# SCH_Breakout_Boards_2023-05-21.net
KiCad netlist of a schematic drawn in EasyEDA
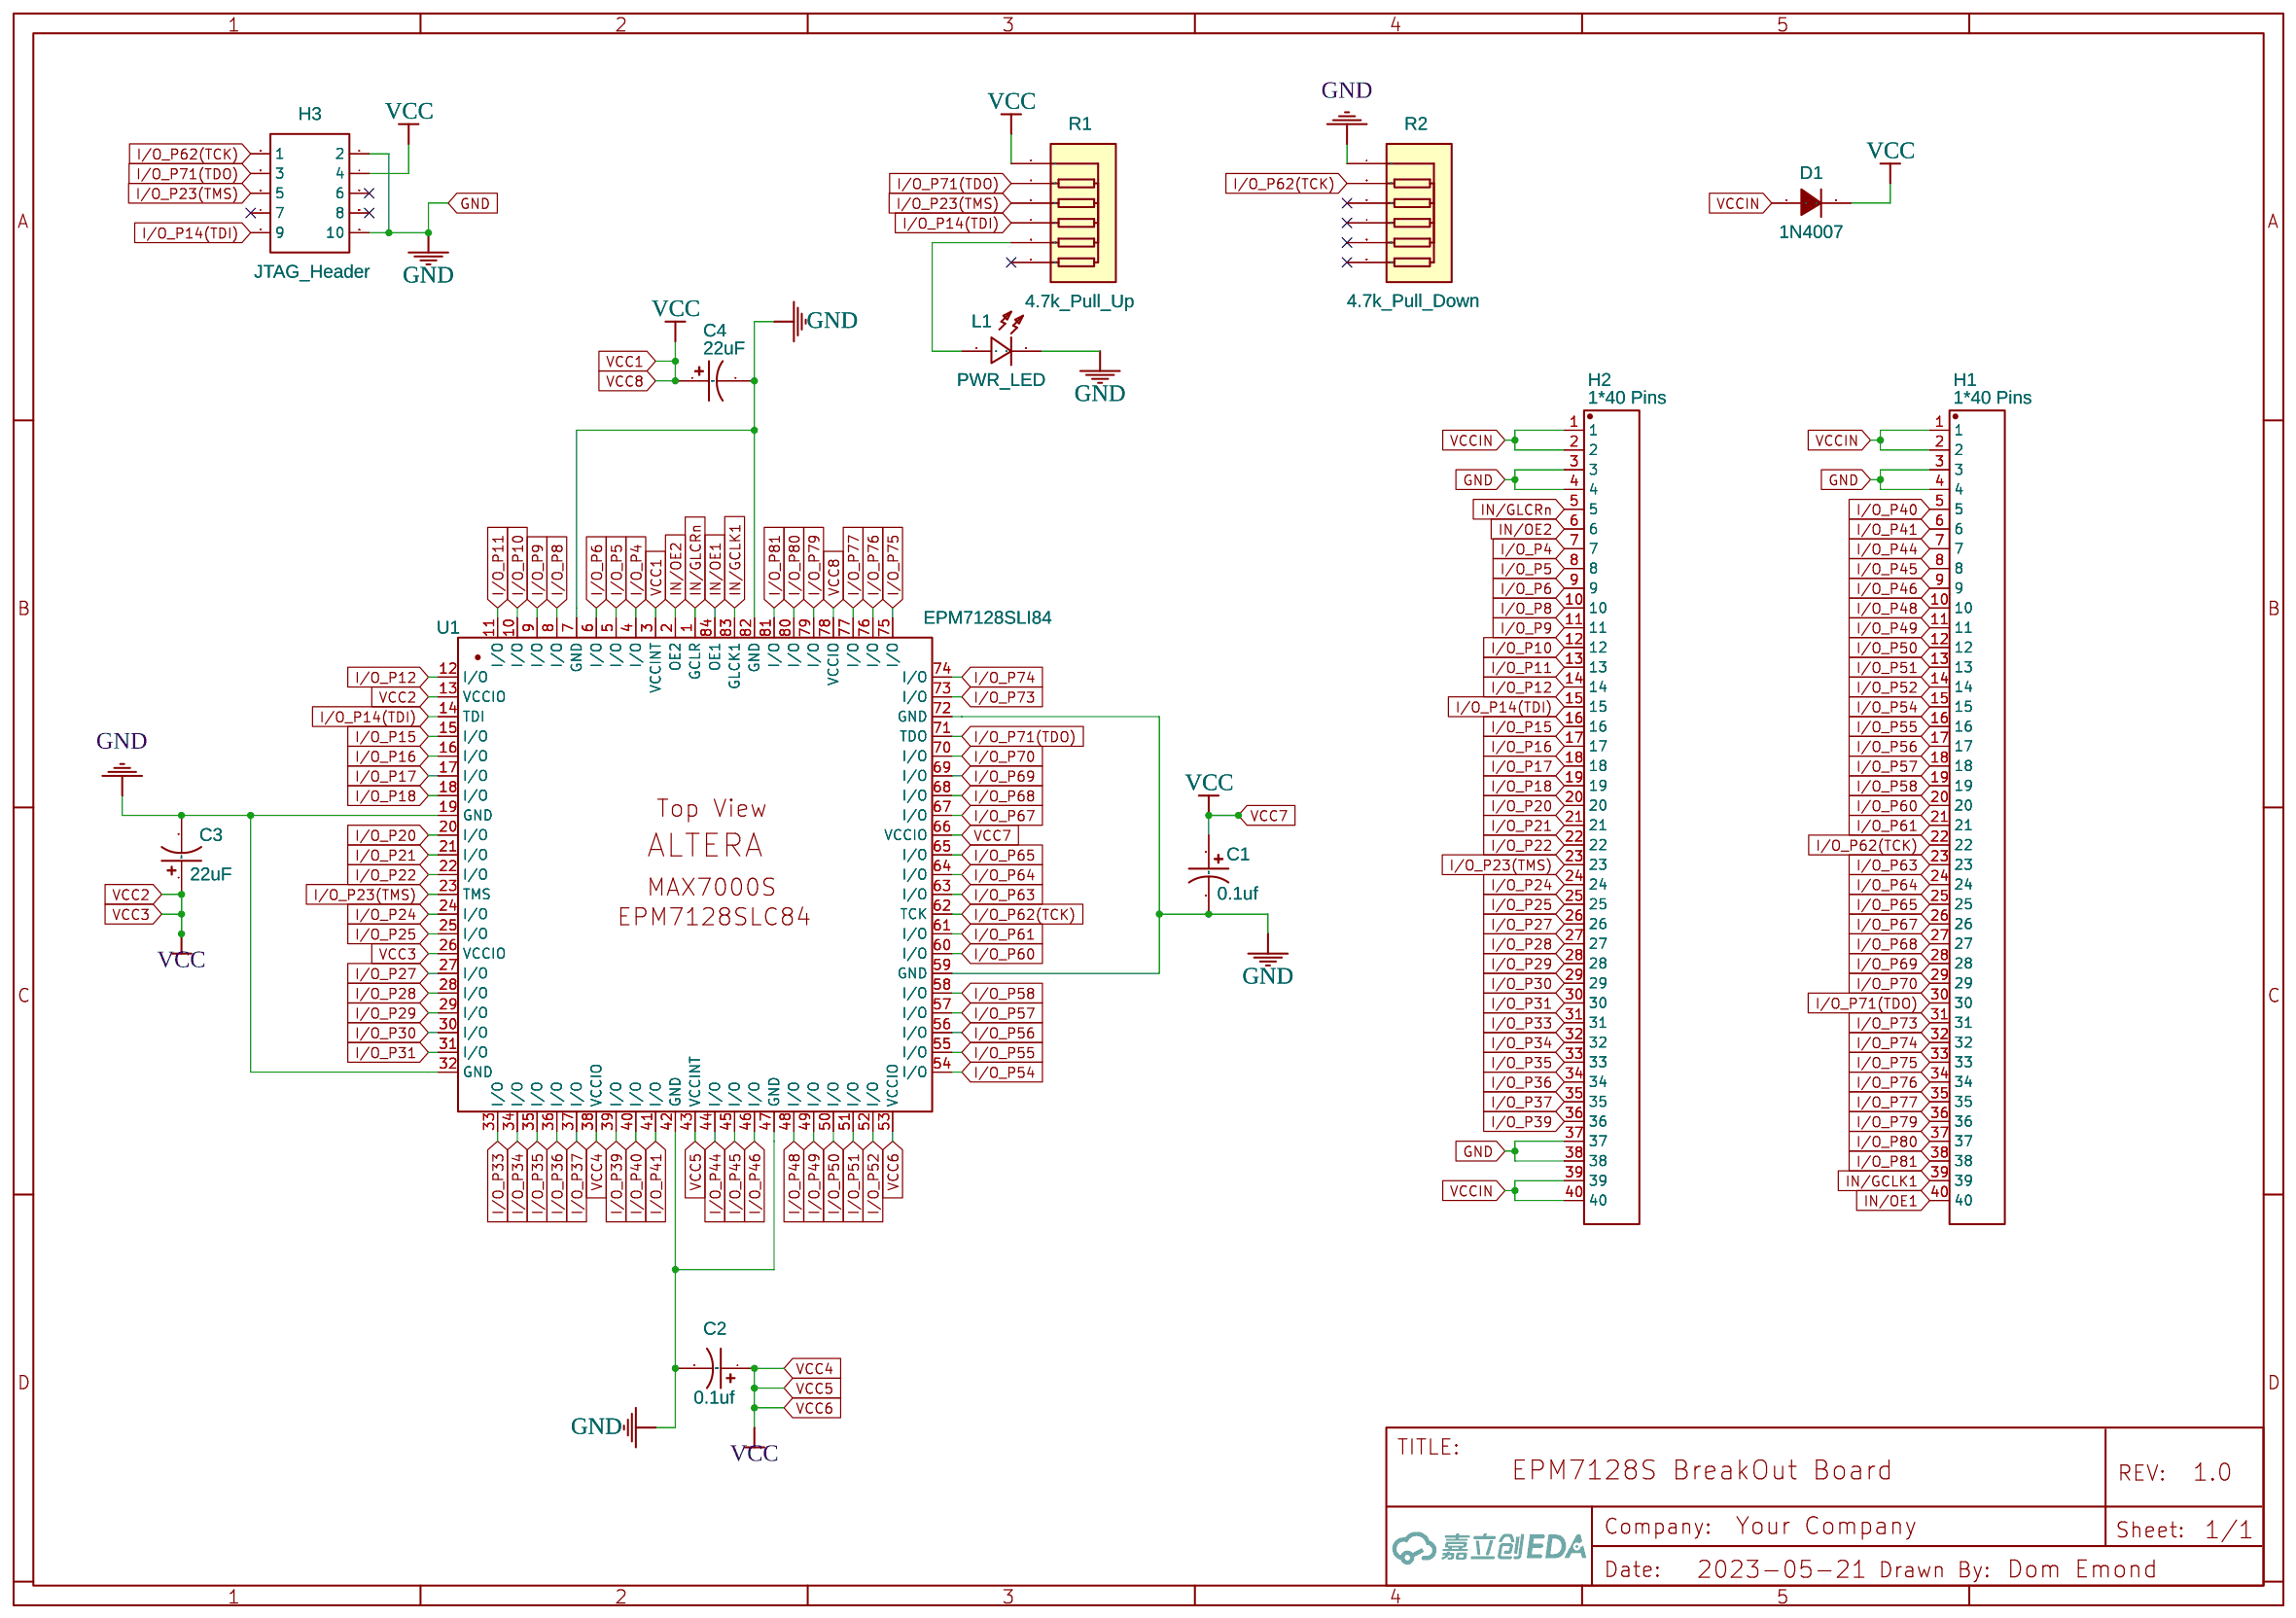
[diagram p0: schematic sheet]

(export (version "E")
  (design (tool "Eeschema 10.0.6"))
  (components
    (comp (ref "C1")
      (value "0.1uf")
      (fields
        (field (name "BOM_Manufacturer Part") "35MH522MEFC6.3X5")
        (field (name "BOM_Supplier Part") "C473191")
      )
      (libsource (lib "") (part "35MH522MEFC6.3X5_3"))
    )
    (comp (ref "C2")
      (value "0.1uf")
      (fields
        (field (name "BOM_Manufacturer Part") "35MH522MEFC6.3X5")
        (field (name "BOM_Supplier Part") "C473191")
      )
      (libsource (lib "") (part "35MH522MEFC6.3X5"))
    )
    (comp (ref "C3")
      (value "22uF")
      (fields
        (field (name "BOM_Manufacturer Part") "35MH522MEFC6.3X5")
        (field (name "BOM_Supplier Part") "C473191")
      )
      (libsource (lib "") (part "35MH522MEFC6.3X5_2"))
    )
    (comp (ref "C4")
      (value "22uF")
      (fields
        (field (name "BOM_Manufacturer Part") "35MH522MEFC6.3X5")
        (field (name "BOM_Supplier Part") "C473191")
      )
      (libsource (lib "") (part "35MH522MEFC6.3X5_1"))
    )
    (comp (ref "D1")
      (value "1N4007")
      (fields (field (name "BOM_Manufacturer Part") "1N4007W") (field (name "BOM_Supplier Part") "C108803"))
      (libsource (lib "") (part "1N4007"))
    )
    (comp (ref "H1")
      (value "1*40 Pins")
      (fields
        (field (name "BOM_Manufacturer Part") "2.54mm 1*40P Reverse bending Headers  Pins")
        (field (name "BOM_Supplier Part") "C29775")
      )
      (libsource (lib "") (part "2.54mm 1*40P Reverse bending Headers  Pins_C29775"))
    )
    (comp (ref "H2")
      (value "1*40 Pins")
      (fields
        (field (name "BOM_Manufacturer Part") "2.54mm 1*40P Reverse bending Headers  Pins")
        (field (name "BOM_Supplier Part") "C29775")
      )
      (libsource (lib "") (part "2.54mm 1*40P Reverse bending Headers  Pins_C29775"))
    )
    (comp (ref "H3")
      (value "JTAG_Header")
      (fields
        (field (name "BOM_Manufacturer Part") "2*5pHeaders  Pins 2.54mm")
        (field (name "BOM_Supplier Part") "C28207")
      )
      (libsource (lib "") (part "Header-Male-2.54_2x5"))
    )
    (comp (ref "L1")
      (value "PWR_LED")
      (fields (field (name "BOM_Manufacturer Part") "LED-2") (field (name "BOM_Supplier Part") "C9900015223"))
      (libsource (lib "") (part "LED-2"))
    )
    (comp (ref "R1")
      (value "4.7k_Pull_Up")
      (fields (field (name "BOM_Manufacturer Part") "A06-102JP") (field (name "BOM_Supplier Part") "C969103"))
      (libsource (lib "") (part "A06-102JP_C969103"))
    )
    (comp (ref "R2")
      (value "4.7k_Pull_Down")
      (fields (field (name "BOM_Manufacturer Part") "A06-102JP") (field (name "BOM_Supplier Part") "C969103"))
      (libsource (lib "") (part "A06-102JP_C969103"))
    )
    (comp (ref "U1")
      (value "EPM7128SLI84")
      (fields
        (field (name "BOM_Manufacturer Part") "EPM7128SLI84-10")
        (field (name "BOM_Supplier Part") "C2829062")
      )
      (libsource (lib "") (part "EPM7128SLI84-10"))
    )
  )
  (nets
    (net (code "1") (name "GND") (class "Default")
      (node (ref "C1") (pin "2") (pinfunction "2_2") (pintype "unspecified"))
      (node (ref "C2") (pin "2") (pinfunction "2_2") (pintype "unspecified"))
      (node (ref "C3") (pin "2") (pinfunction "2_2") (pintype "unspecified"))
      (node (ref "C4") (pin "2") (pinfunction "2_2") (pintype "unspecified"))
      (node (ref "H1") (pin "3") (pinfunction "3_3") (pintype "unspecified"))
      (node (ref "H1") (pin "4") (pinfunction "4_4") (pintype "unspecified"))
      (node (ref "H2") (pin "3") (pinfunction "3_3") (pintype "unspecified"))
      (node (ref "H2") (pin "37") (pinfunction "37_37") (pintype "unspecified"))
      (node (ref "H2") (pin "38") (pinfunction "38_38") (pintype "unspecified"))
      (node (ref "H2") (pin "4") (pinfunction "4_4") (pintype "unspecified"))
      (node (ref "H3") (pin "10") (pinfunction "10_10") (pintype "input"))
      (node (ref "H3") (pin "2") (pinfunction "2_2") (pintype "input"))
      (node (ref "L1") (pin "1") (pinfunction "E_1") (pintype "unspecified"))
      (node (ref "R2") (pin "1") (pinfunction "1_1") (pintype "input"))
      (node (ref "U1") (pin "19") (pinfunction "GND_19") (pintype "bidirectional"))
      (node (ref "U1") (pin "32") (pinfunction "GND_32") (pintype "bidirectional"))
      (node (ref "U1") (pin "42") (pinfunction "GND_42") (pintype "bidirectional"))
      (node (ref "U1") (pin "47") (pinfunction "GND_47") (pintype "bidirectional"))
      (node (ref "U1") (pin "59") (pinfunction "GND_59") (pintype "passive"))
      (node (ref "U1") (pin "7") (pinfunction "GND_7") (pintype "bidirectional"))
      (node (ref "U1") (pin "72") (pinfunction "GND_72") (pintype "bidirectional"))
      (node (ref "U1") (pin "82") (pinfunction "GND_82") (pintype "passive"))
    )
    (net (code "2") (name "IN{slash}GCLK1") (class "Default")
      (node (ref "H1") (pin "39") (pinfunction "39_39") (pintype "unspecified"))
      (node (ref "U1") (pin "83") (pinfunction "GLCK1_83") (pintype "bidirectional"))
    )
    (net (code "3") (name "IN{slash}GLCRn") (class "Default")
      (node (ref "H2") (pin "5") (pinfunction "5_5") (pintype "unspecified"))
      (node (ref "U1") (pin "1") (pinfunction "GCLR_1") (pintype "bidirectional"))
    )
    (net (code "4") (name "IN{slash}OE1") (class "Default")
      (node (ref "H1") (pin "40") (pinfunction "40_40") (pintype "unspecified"))
      (node (ref "U1") (pin "84") (pinfunction "OE1_84") (pintype "bidirectional"))
    )
    (net (code "5") (name "IN{slash}OE2") (class "Default")
      (node (ref "H2") (pin "6") (pinfunction "6_6") (pintype "unspecified"))
      (node (ref "U1") (pin "2") (pinfunction "OE2_2") (pintype "bidirectional"))
    )
    (net (code "6") (name "I{slash}O_P4") (class "Default")
      (node (ref "H2") (pin "7") (pinfunction "7_7") (pintype "unspecified"))
      (node (ref "U1") (pin "4") (pinfunction "I/O_4") (pintype "bidirectional"))
    )
    (net (code "7") (name "I{slash}O_P5") (class "Default")
      (node (ref "H2") (pin "8") (pinfunction "8_8") (pintype "unspecified"))
      (node (ref "U1") (pin "5") (pinfunction "I/O_5") (pintype "bidirectional"))
    )
    (net (code "8") (name "I{slash}O_P6") (class "Default")
      (node (ref "H2") (pin "9") (pinfunction "9_9") (pintype "unspecified"))
      (node (ref "U1") (pin "6") (pinfunction "I/O_6") (pintype "bidirectional"))
    )
    (net (code "9") (name "I{slash}O_P8") (class "Default")
      (node (ref "H2") (pin "10") (pinfunction "10_10") (pintype "unspecified"))
      (node (ref "U1") (pin "8") (pinfunction "I/O_8") (pintype "bidirectional"))
    )
    (net (code "10") (name "I{slash}O_P9") (class "Default")
      (node (ref "H2") (pin "11") (pinfunction "11_11") (pintype "unspecified"))
      (node (ref "U1") (pin "9") (pinfunction "I/O_9") (pintype "bidirectional"))
    )
    (net (code "11") (name "I{slash}O_P10") (class "Default")
      (node (ref "H2") (pin "12") (pinfunction "12_12") (pintype "unspecified"))
      (node (ref "U1") (pin "10") (pinfunction "I/O_10") (pintype "bidirectional"))
    )
    (net (code "12") (name "I{slash}O_P11") (class "Default")
      (node (ref "H2") (pin "13") (pinfunction "13_13") (pintype "unspecified"))
      (node (ref "U1") (pin "11") (pinfunction "I/O_11") (pintype "passive"))
    )
    (net (code "13") (name "I{slash}O_P12") (class "Default")
      (node (ref "H2") (pin "14") (pinfunction "14_14") (pintype "unspecified"))
      (node (ref "U1") (pin "12") (pinfunction "I/O_12") (pintype "bidirectional"))
    )
    (net (code "14") (name "I{slash}O_P14(TDI)") (class "Default")
      (node (ref "H2") (pin "15") (pinfunction "15_15") (pintype "unspecified"))
      (node (ref "H3") (pin "9") (pinfunction "9_9") (pintype "input"))
      (node (ref "R1") (pin "4") (pinfunction "4_4") (pintype "input"))
      (node (ref "U1") (pin "14") (pinfunction "TDI_14") (pintype "bidirectional"))
    )
    (net (code "15") (name "I{slash}O_P15") (class "Default")
      (node (ref "H2") (pin "16") (pinfunction "16_16") (pintype "unspecified"))
      (node (ref "U1") (pin "15") (pinfunction "I/O_15") (pintype "bidirectional"))
    )
    (net (code "16") (name "I{slash}O_P16") (class "Default")
      (node (ref "H2") (pin "17") (pinfunction "17_17") (pintype "unspecified"))
      (node (ref "U1") (pin "16") (pinfunction "I/O_16") (pintype "bidirectional"))
    )
    (net (code "17") (name "I{slash}O_P17") (class "Default")
      (node (ref "H2") (pin "18") (pinfunction "18_18") (pintype "unspecified"))
      (node (ref "U1") (pin "17") (pinfunction "I/O_17") (pintype "bidirectional"))
    )
    (net (code "18") (name "I{slash}O_P18") (class "Default")
      (node (ref "H2") (pin "19") (pinfunction "19_19") (pintype "unspecified"))
      (node (ref "U1") (pin "18") (pinfunction "I/O_18") (pintype "passive"))
    )
    (net (code "19") (name "I{slash}O_P20") (class "Default")
      (node (ref "H2") (pin "20") (pinfunction "20_20") (pintype "unspecified"))
      (node (ref "U1") (pin "20") (pinfunction "I/O_20") (pintype "bidirectional"))
    )
    (net (code "20") (name "I{slash}O_P21") (class "Default")
      (node (ref "H2") (pin "21") (pinfunction "21_21") (pintype "unspecified"))
      (node (ref "U1") (pin "21") (pinfunction "I/O_21") (pintype "bidirectional"))
    )
    (net (code "21") (name "I{slash}O_P22") (class "Default")
      (node (ref "H2") (pin "22") (pinfunction "22_22") (pintype "unspecified"))
      (node (ref "U1") (pin "22") (pinfunction "I/O_22") (pintype "bidirectional"))
    )
    (net (code "22") (name "I{slash}O_P23(TMS)") (class "Default")
      (node (ref "H2") (pin "23") (pinfunction "23_23") (pintype "unspecified"))
      (node (ref "H3") (pin "5") (pinfunction "5_5") (pintype "input"))
      (node (ref "R1") (pin "3") (pinfunction "3_3") (pintype "input"))
      (node (ref "U1") (pin "23") (pinfunction "TMS_23") (pintype "bidirectional"))
    )
    (net (code "23") (name "I{slash}O_P24") (class "Default")
      (node (ref "H2") (pin "24") (pinfunction "24_24") (pintype "unspecified"))
      (node (ref "U1") (pin "24") (pinfunction "I/O_24") (pintype "bidirectional"))
    )
    (net (code "24") (name "I{slash}O_P25") (class "Default")
      (node (ref "H2") (pin "25") (pinfunction "25_25") (pintype "unspecified"))
      (node (ref "U1") (pin "25") (pinfunction "I/O_25") (pintype "bidirectional"))
    )
    (net (code "25") (name "I{slash}O_P27") (class "Default")
      (node (ref "H2") (pin "26") (pinfunction "26_26") (pintype "unspecified"))
      (node (ref "U1") (pin "27") (pinfunction "I/O_27") (pintype "bidirectional"))
    )
    (net (code "26") (name "I{slash}O_P28") (class "Default")
      (node (ref "H2") (pin "27") (pinfunction "27_27") (pintype "unspecified"))
      (node (ref "U1") (pin "28") (pinfunction "I/O_28") (pintype "bidirectional"))
    )
    (net (code "27") (name "I{slash}O_P29") (class "Default")
      (node (ref "H2") (pin "28") (pinfunction "28_28") (pintype "unspecified"))
      (node (ref "U1") (pin "29") (pinfunction "I/O_29") (pintype "bidirectional"))
    )
    (net (code "28") (name "I{slash}O_P30") (class "Default")
      (node (ref "H2") (pin "29") (pinfunction "29_29") (pintype "unspecified"))
      (node (ref "U1") (pin "30") (pinfunction "I/O_30") (pintype "bidirectional"))
    )
    (net (code "29") (name "I{slash}O_P31") (class "Default")
      (node (ref "H2") (pin "30") (pinfunction "30_30") (pintype "unspecified"))
      (node (ref "U1") (pin "31") (pinfunction "I/O_31") (pintype "bidirectional"))
    )
    (net (code "30") (name "I{slash}O_P33") (class "Default")
      (node (ref "H2") (pin "31") (pinfunction "31_31") (pintype "unspecified"))
      (node (ref "U1") (pin "33") (pinfunction "I/O_33") (pintype "bidirectional"))
    )
    (net (code "31") (name "I{slash}O_P34") (class "Default")
      (node (ref "H2") (pin "32") (pinfunction "32_32") (pintype "unspecified"))
      (node (ref "U1") (pin "34") (pinfunction "I/O_34") (pintype "passive"))
    )
    (net (code "32") (name "I{slash}O_P35") (class "Default")
      (node (ref "H2") (pin "33") (pinfunction "33_33") (pintype "unspecified"))
      (node (ref "U1") (pin "35") (pinfunction "I/O_35") (pintype "bidirectional"))
    )
    (net (code "33") (name "I{slash}O_P36") (class "Default")
      (node (ref "H2") (pin "34") (pinfunction "34_34") (pintype "unspecified"))
      (node (ref "U1") (pin "36") (pinfunction "I/O_36") (pintype "bidirectional"))
    )
    (net (code "34") (name "I{slash}O_P37") (class "Default")
      (node (ref "H2") (pin "35") (pinfunction "35_35") (pintype "unspecified"))
      (node (ref "U1") (pin "37") (pinfunction "I/O_37") (pintype "bidirectional"))
    )
    (net (code "35") (name "I{slash}O_P39") (class "Default")
      (node (ref "H2") (pin "36") (pinfunction "36_36") (pintype "unspecified"))
      (node (ref "U1") (pin "39") (pinfunction "I/O_39") (pintype "passive"))
    )
    (net (code "36") (name "I{slash}O_P40") (class "Default")
      (node (ref "H1") (pin "5") (pinfunction "5_5") (pintype "unspecified"))
      (node (ref "U1") (pin "40") (pinfunction "I/O_40") (pintype "bidirectional"))
    )
    (net (code "37") (name "I{slash}O_P41") (class "Default")
      (node (ref "H1") (pin "6") (pinfunction "6_6") (pintype "unspecified"))
      (node (ref "U1") (pin "41") (pinfunction "I/O_41") (pintype "bidirectional"))
    )
    (net (code "38") (name "I{slash}O_P44") (class "Default")
      (node (ref "H1") (pin "7") (pinfunction "7_7") (pintype "unspecified"))
      (node (ref "U1") (pin "44") (pinfunction "I/O_44") (pintype "bidirectional"))
    )
    (net (code "39") (name "I{slash}O_P45") (class "Default")
      (node (ref "H1") (pin "8") (pinfunction "8_8") (pintype "unspecified"))
      (node (ref "U1") (pin "45") (pinfunction "I/O_45") (pintype "bidirectional"))
    )
    (net (code "40") (name "I{slash}O_P46") (class "Default")
      (node (ref "H1") (pin "9") (pinfunction "9_9") (pintype "unspecified"))
      (node (ref "U1") (pin "46") (pinfunction "I/O_46") (pintype "bidirectional"))
    )
    (net (code "41") (name "I{slash}O_P48") (class "Default")
      (node (ref "H1") (pin "10") (pinfunction "10_10") (pintype "unspecified"))
      (node (ref "U1") (pin "48") (pinfunction "I/O_48") (pintype "bidirectional"))
    )
    (net (code "42") (name "I{slash}O_P49") (class "Default")
      (node (ref "H1") (pin "11") (pinfunction "11_11") (pintype "unspecified"))
      (node (ref "U1") (pin "49") (pinfunction "I/O_49") (pintype "bidirectional"))
    )
    (net (code "43") (name "I{slash}O_P50") (class "Default")
      (node (ref "H1") (pin "12") (pinfunction "12_12") (pintype "unspecified"))
      (node (ref "U1") (pin "50") (pinfunction "I/O_50") (pintype "bidirectional"))
    )
    (net (code "44") (name "I{slash}O_P51") (class "Default")
      (node (ref "H1") (pin "13") (pinfunction "13_13") (pintype "unspecified"))
      (node (ref "U1") (pin "51") (pinfunction "I/O_51") (pintype "passive"))
    )
    (net (code "45") (name "I{slash}O_P52") (class "Default")
      (node (ref "H1") (pin "14") (pinfunction "14_14") (pintype "unspecified"))
      (node (ref "U1") (pin "52") (pinfunction "I/O_52") (pintype "bidirectional"))
    )
    (net (code "46") (name "I{slash}O_P54") (class "Default")
      (node (ref "H1") (pin "15") (pinfunction "15_15") (pintype "unspecified"))
      (node (ref "U1") (pin "54") (pinfunction "I/O_54") (pintype "bidirectional"))
    )
    (net (code "47") (name "I{slash}O_P55") (class "Default")
      (node (ref "H1") (pin "16") (pinfunction "16_16") (pintype "unspecified"))
      (node (ref "U1") (pin "55") (pinfunction "I/O_55") (pintype "bidirectional"))
    )
    (net (code "48") (name "I{slash}O_P56") (class "Default")
      (node (ref "H1") (pin "17") (pinfunction "17_17") (pintype "unspecified"))
      (node (ref "U1") (pin "56") (pinfunction "I/O_56") (pintype "bidirectional"))
    )
    (net (code "49") (name "I{slash}O_P57") (class "Default")
      (node (ref "H1") (pin "18") (pinfunction "18_18") (pintype "unspecified"))
      (node (ref "U1") (pin "57") (pinfunction "I/O_57") (pintype "bidirectional"))
    )
    (net (code "50") (name "I{slash}O_P58") (class "Default")
      (node (ref "H1") (pin "19") (pinfunction "19_19") (pintype "unspecified"))
      (node (ref "U1") (pin "58") (pinfunction "I/O_58") (pintype "bidirectional"))
    )
    (net (code "51") (name "I{slash}O_P60") (class "Default")
      (node (ref "H1") (pin "20") (pinfunction "20_20") (pintype "unspecified"))
      (node (ref "U1") (pin "60") (pinfunction "I/O_60") (pintype "bidirectional"))
    )
    (net (code "52") (name "I{slash}O_P61") (class "Default")
      (node (ref "H1") (pin "21") (pinfunction "21_21") (pintype "unspecified"))
      (node (ref "U1") (pin "61") (pinfunction "I/O_61") (pintype "bidirectional"))
    )
    (net (code "53") (name "I{slash}O_P62(TCK)") (class "Default")
      (node (ref "H1") (pin "22") (pinfunction "22_22") (pintype "unspecified"))
      (node (ref "H3") (pin "1") (pinfunction "1_1") (pintype "input"))
      (node (ref "R2") (pin "2") (pinfunction "2_2") (pintype "input"))
      (node (ref "U1") (pin "62") (pinfunction "TCK_62") (pintype "bidirectional"))
    )
    (net (code "54") (name "I{slash}O_P63") (class "Default")
      (node (ref "H1") (pin "23") (pinfunction "23_23") (pintype "unspecified"))
      (node (ref "U1") (pin "63") (pinfunction "I/O_63") (pintype "bidirectional"))
    )
    (net (code "55") (name "I{slash}O_P64") (class "Default")
      (node (ref "H1") (pin "24") (pinfunction "24_24") (pintype "unspecified"))
      (node (ref "U1") (pin "64") (pinfunction "I/O_64") (pintype "bidirectional"))
    )
    (net (code "56") (name "I{slash}O_P65") (class "Default")
      (node (ref "H1") (pin "25") (pinfunction "25_25") (pintype "unspecified"))
      (node (ref "U1") (pin "65") (pinfunction "I/O_65") (pintype "bidirectional"))
    )
    (net (code "57") (name "I{slash}O_P67") (class "Default")
      (node (ref "H1") (pin "26") (pinfunction "26_26") (pintype "unspecified"))
      (node (ref "U1") (pin "67") (pinfunction "I/O_67") (pintype "bidirectional"))
    )
    (net (code "58") (name "I{slash}O_P68") (class "Default")
      (node (ref "H1") (pin "27") (pinfunction "27_27") (pintype "unspecified"))
      (node (ref "U1") (pin "68") (pinfunction "I/O_68") (pintype "bidirectional"))
    )
    (net (code "59") (name "I{slash}O_P69") (class "Default")
      (node (ref "H1") (pin "28") (pinfunction "28_28") (pintype "unspecified"))
      (node (ref "U1") (pin "69") (pinfunction "I/O_69") (pintype "bidirectional"))
    )
    (net (code "60") (name "I{slash}O_P70") (class "Default")
      (node (ref "H1") (pin "29") (pinfunction "29_29") (pintype "unspecified"))
      (node (ref "U1") (pin "70") (pinfunction "I/O_70") (pintype "bidirectional"))
    )
    (net (code "61") (name "I{slash}O_P71(TDO)") (class "Default")
      (node (ref "H1") (pin "30") (pinfunction "30_30") (pintype "unspecified"))
      (node (ref "H3") (pin "3") (pinfunction "3_3") (pintype "input"))
      (node (ref "R1") (pin "2") (pinfunction "2_2") (pintype "input"))
      (node (ref "U1") (pin "71") (pinfunction "TDO_71") (pintype "bidirectional"))
    )
    (net (code "62") (name "I{slash}O_P73") (class "Default")
      (node (ref "H1") (pin "31") (pinfunction "31_31") (pintype "unspecified"))
      (node (ref "U1") (pin "73") (pinfunction "I/O_73") (pintype "bidirectional"))
    )
    (net (code "63") (name "I{slash}O_P74") (class "Default")
      (node (ref "H1") (pin "32") (pinfunction "32_32") (pintype "unspecified"))
      (node (ref "U1") (pin "74") (pinfunction "I/O_74") (pintype "passive"))
    )
    (net (code "64") (name "I{slash}O_P75") (class "Default")
      (node (ref "H1") (pin "33") (pinfunction "33_33") (pintype "unspecified"))
      (node (ref "U1") (pin "75") (pinfunction "I/O_75") (pintype "bidirectional"))
    )
    (net (code "65") (name "I{slash}O_P76") (class "Default")
      (node (ref "H1") (pin "34") (pinfunction "34_34") (pintype "unspecified"))
      (node (ref "U1") (pin "76") (pinfunction "I/O_76") (pintype "bidirectional"))
    )
    (net (code "66") (name "I{slash}O_P77") (class "Default")
      (node (ref "H1") (pin "35") (pinfunction "35_35") (pintype "unspecified"))
      (node (ref "U1") (pin "77") (pinfunction "I/O_77") (pintype "bidirectional"))
    )
    (net (code "67") (name "I{slash}O_P79") (class "Default")
      (node (ref "H1") (pin "36") (pinfunction "36_36") (pintype "unspecified"))
      (node (ref "U1") (pin "79") (pinfunction "I/O_79") (pintype "bidirectional"))
    )
    (net (code "68") (name "I{slash}O_P80") (class "Default")
      (node (ref "H1") (pin "37") (pinfunction "37_37") (pintype "unspecified"))
      (node (ref "U1") (pin "80") (pinfunction "I/O_80") (pintype "bidirectional"))
    )
    (net (code "69") (name "I{slash}O_P81") (class "Default")
      (node (ref "H1") (pin "38") (pinfunction "38_38") (pintype "unspecified"))
      (node (ref "U1") (pin "81") (pinfunction "I/O_81") (pintype "bidirectional"))
    )
    (net (code "70") (name "Net-(L1-C)") (class "Default")
      (node (ref "L1") (pin "2") (pinfunction "C_2") (pintype "unspecified"))
      (node (ref "R1") (pin "5") (pinfunction "5_5") (pintype "input"))
    )
    (net (code "71") (name "VCC1") (class "Default")
      (node (ref "C1") (pin "1") (pinfunction "1_1") (pintype "unspecified"))
      (node (ref "C2") (pin "1") (pinfunction "1_1") (pintype "unspecified"))
      (node (ref "C3") (pin "1") (pinfunction "1_1") (pintype "unspecified"))
      (node (ref "C4") (pin "1") (pinfunction "1_1") (pintype "unspecified"))
      (node (ref "D1") (pin "2") (pinfunction "K_2") (pintype "unspecified"))
      (node (ref "H3") (pin "4") (pinfunction "4_4") (pintype "input"))
      (node (ref "R1") (pin "1") (pinfunction "1_1") (pintype "input"))
      (node (ref "U1") (pin "13") (pinfunction "VCCIO_13") (pintype "bidirectional"))
      (node (ref "U1") (pin "26") (pinfunction "VCCIO_26") (pintype "passive"))
      (node (ref "U1") (pin "3") (pinfunction "VCCINT_3") (pintype "passive"))
      (node (ref "U1") (pin "38") (pinfunction "VCCIO_38") (pintype "passive"))
      (node (ref "U1") (pin "43") (pinfunction "VCCINT_43") (pintype "passive"))
      (node (ref "U1") (pin "53") (pinfunction "VCCIO_53") (pintype "bidirectional"))
      (node (ref "U1") (pin "66") (pinfunction "VCCIO_66") (pintype "passive"))
      (node (ref "U1") (pin "78") (pinfunction "VCCIO_78") (pintype "bidirectional"))
    )
    (net (code "72") (name "VCCIN") (class "Default")
      (node (ref "D1") (pin "1") (pinfunction "A_1") (pintype "unspecified"))
      (node (ref "H1") (pin "1") (pinfunction "1_1") (pintype "unspecified"))
      (node (ref "H1") (pin "2") (pinfunction "2_2") (pintype "unspecified"))
      (node (ref "H2") (pin "1") (pinfunction "1_1") (pintype "unspecified"))
      (node (ref "H2") (pin "2") (pinfunction "2_2") (pintype "unspecified"))
      (node (ref "H2") (pin "39") (pinfunction "39_39") (pintype "unspecified"))
      (node (ref "H2") (pin "40") (pinfunction "40_40") (pintype "unspecified"))
    )
    (net (code "73") (name "unconnected-(H3-Pad6)") (class "Default")
      (node (ref "H3") (pin "6") (pinfunction "6_6") (pintype "input+no_connect"))
    )
    (net (code "74") (name "unconnected-(H3-Pad7)") (class "Default")
      (node (ref "H3") (pin "7") (pinfunction "7_7") (pintype "input+no_connect"))
    )
    (net (code "75") (name "unconnected-(H3-Pad8)") (class "Default")
      (node (ref "H3") (pin "8") (pinfunction "8_8") (pintype "input+no_connect"))
    )
    (net (code "76") (name "unconnected-(R1-Pad6)") (class "Default")
      (node (ref "R1") (pin "6") (pinfunction "6_6") (pintype "input+no_connect"))
    )
    (net (code "77") (name "unconnected-(R2-Pad3)") (class "Default")
      (node (ref "R2") (pin "3") (pinfunction "3_3") (pintype "input+no_connect"))
    )
    (net (code "78") (name "unconnected-(R2-Pad4)") (class "Default")
      (node (ref "R2") (pin "4") (pinfunction "4_4") (pintype "input+no_connect"))
    )
    (net (code "79") (name "unconnected-(R2-Pad5)") (class "Default")
      (node (ref "R2") (pin "5") (pinfunction "5_5") (pintype "input+no_connect"))
    )
    (net (code "80") (name "unconnected-(R2-Pad6)") (class "Default")
      (node (ref "R2") (pin "6") (pinfunction "6_6") (pintype "input+no_connect"))
    )
  )
)
